# nRF51822.net
KiCad netlist of a schematic drawn in EAGLE
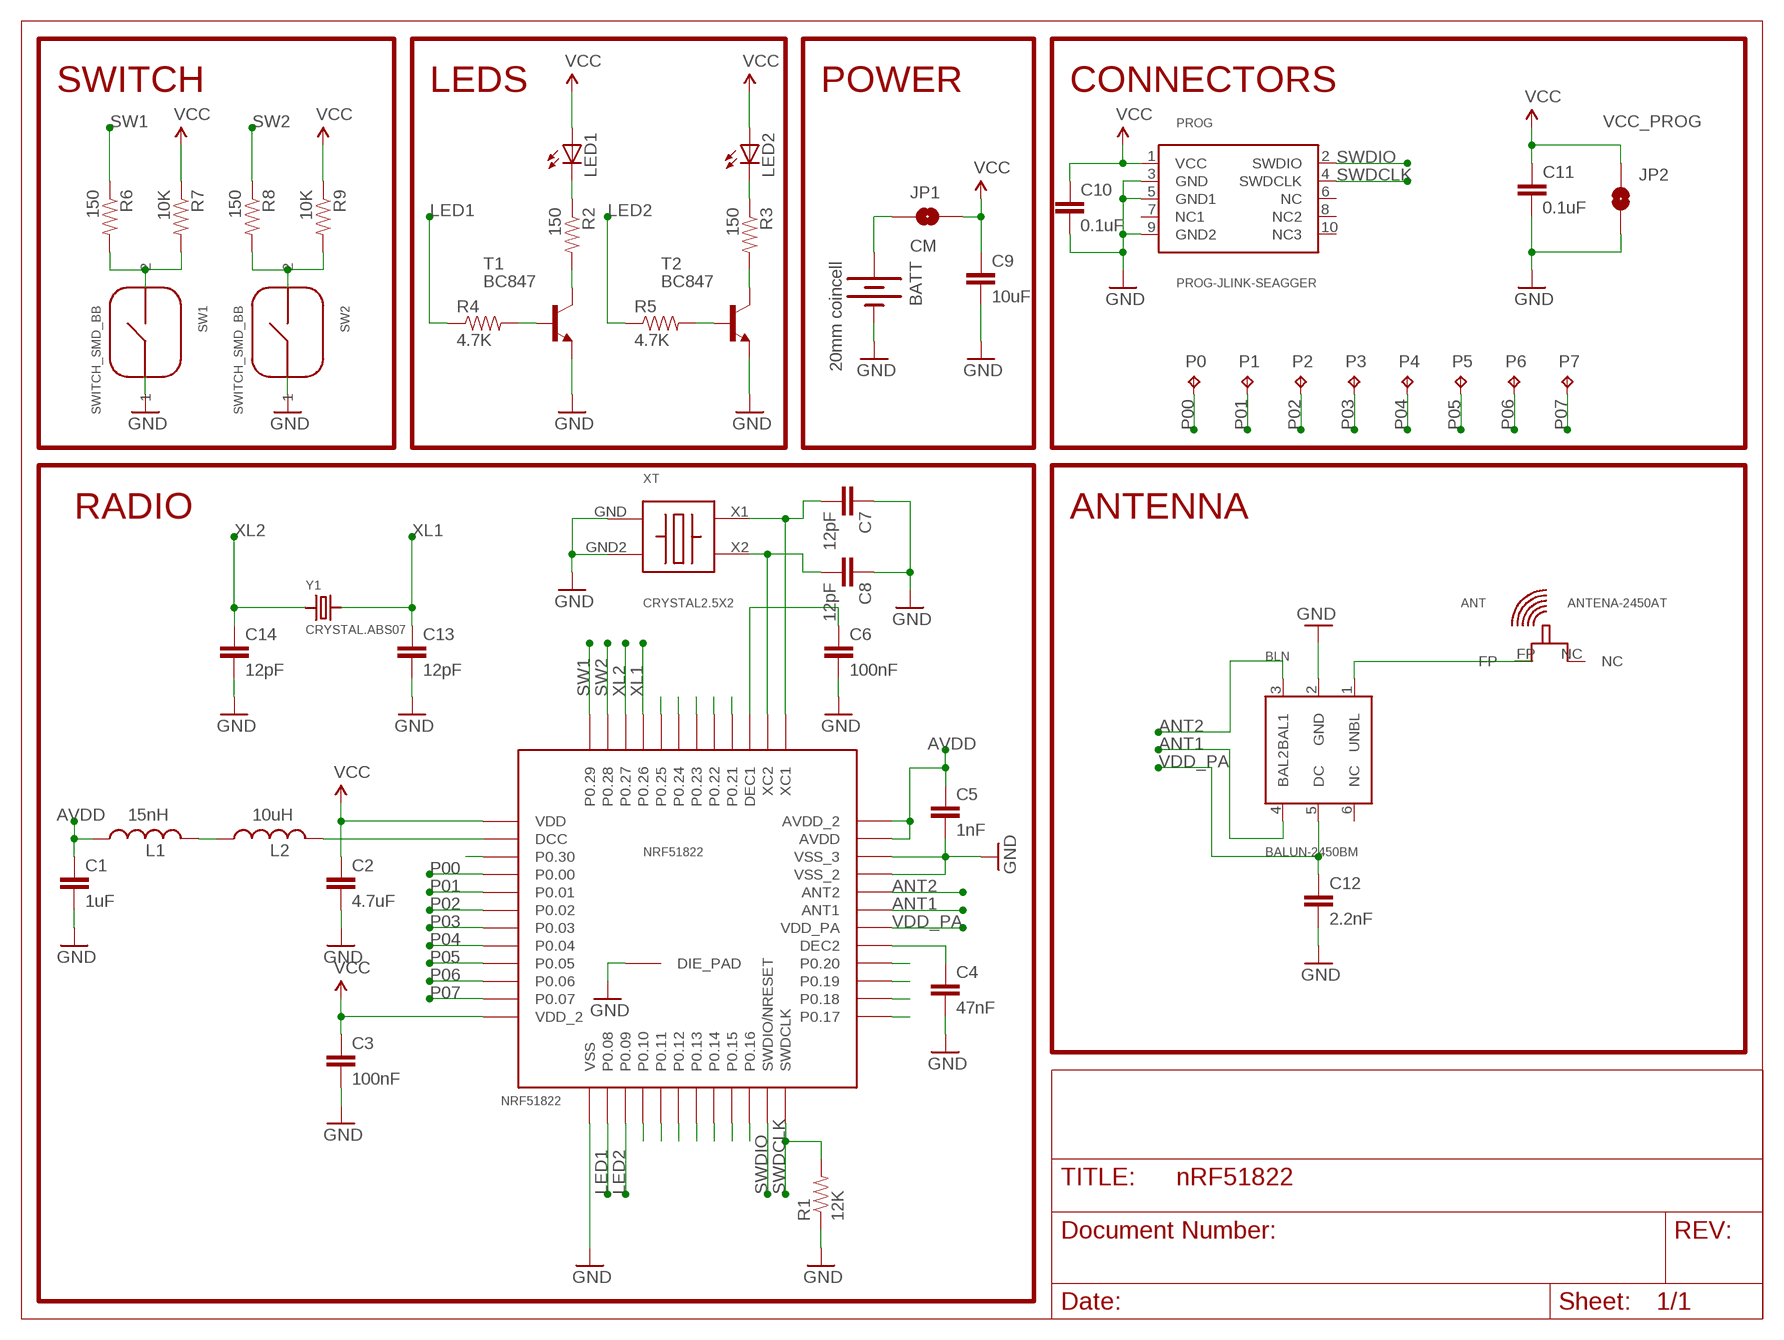
[diagram p0: schematic, sheet 1]

(export (version "E")
  (design (tool "Eeschema 10.0.6"))
  (components
    (comp (ref "ANT")
      (value "ANTENA-2450AT")
      (footprint "eagle-import:2450AT18B100")
      (libsource (lib "eagle-import") (part "ANTENA-2450AT"))
    )
    (comp (ref "BATT")
      (value "20mm coincell")
      (footprint "eagle-import:BATTCON_20MM_4LEGS_OVERPASTE")
      (libsource (lib "eagle-import") (part "BATTERY20MM_4LEGS_OVERPASTE"))
    )
    (comp (ref "BLN")
      (value "BALUN-2450BM")
      (footprint "eagle-import:2450BM14A0002")
      (libsource (lib "eagle-import") (part "BALUN-2450BM"))
    )
    (comp (ref "C1")
      (value "1uF")
      (footprint "eagle-import:0603-CAP")
      (libsource (lib "eagle-import") (part "CAP0603-CAP"))
    )
    (comp (ref "C2")
      (value "4.7uF")
      (footprint "eagle-import:0603-CAP")
      (libsource (lib "eagle-import") (part "CAP0603-CAP"))
    )
    (comp (ref "C3")
      (value "100nF")
      (footprint "eagle-import:0603-CAP")
      (libsource (lib "eagle-import") (part "CAP0603-CAP"))
    )
    (comp (ref "C4")
      (value "47nF")
      (footprint "eagle-import:0603-CAP")
      (libsource (lib "eagle-import") (part "CAP0603-CAP"))
    )
    (comp (ref "C5")
      (value "1nF")
      (footprint "eagle-import:0603-CAP")
      (libsource (lib "eagle-import") (part "CAP0603-CAP"))
    )
    (comp (ref "C6")
      (value "100nF")
      (footprint "eagle-import:0603-CAP")
      (libsource (lib "eagle-import") (part "CAP0603-CAP"))
    )
    (comp (ref "C7")
      (value "12pF")
      (footprint "eagle-import:0603-CAP")
      (libsource (lib "eagle-import") (part "CAP0603-CAP"))
    )
    (comp (ref "C8")
      (value "12pF")
      (footprint "eagle-import:0603-CAP")
      (libsource (lib "eagle-import") (part "CAP0603-CAP"))
    )
    (comp (ref "C9")
      (value "10uF")
      (footprint "eagle-import:0603-CAP")
      (libsource (lib "eagle-import") (part "CAP0603-CAP"))
    )
    (comp (ref "C10")
      (value "0.1uF")
      (footprint "eagle-import:0603-CAP")
      (libsource (lib "eagle-import") (part "CAP0603-CAP"))
    )
    (comp (ref "C11")
      (value "0.1uF")
      (footprint "eagle-import:0603-CAP")
      (libsource (lib "eagle-import") (part "CAP0603-CAP"))
    )
    (comp (ref "C12")
      (value "2.2nF")
      (footprint "eagle-import:0603-CAP")
      (libsource (lib "eagle-import") (part "CAP0603-CAP"))
    )
    (comp (ref "C13")
      (value "12pF")
      (footprint "eagle-import:0603-CAP")
      (libsource (lib "eagle-import") (part "CAP0603-CAP"))
    )
    (comp (ref "C14")
      (value "12pF")
      (footprint "eagle-import:0603-CAP")
      (libsource (lib "eagle-import") (part "CAP0603-CAP"))
    )
    (comp (ref "JP1")
      (value "CM")
      (footprint "eagle-import:JUMP-0.05-SMD")
      (libsource (lib "eagle-import") (part "JUMP_SMDPITCH_0.05"))
    )
    (comp (ref "JP2")
      (value "VCC_PROG")
      (footprint "eagle-import:JUMP-0.05-SMD")
      (libsource (lib "eagle-import") (part "JUMP_SMDPITCH_0.05"))
    )
    (comp (ref "L1")
      (value "15nH")
      (footprint "eagle-import:0603")
      (libsource (lib "eagle-import") (part "INDUCTOR0603"))
    )
    (comp (ref "L2")
      (value "10uH")
      (footprint "eagle-import:0603")
      (libsource (lib "eagle-import") (part "INDUCTOR0603"))
    )
    (comp (ref "LED1")
      (value "LED0603")
      (footprint "eagle-import:LED-0603")
      (libsource (lib "eagle-import") (part "LED0603"))
    )
    (comp (ref "LED2")
      (value "LED0603")
      (footprint "eagle-import:LED-0603")
      (libsource (lib "eagle-import") (part "LED0603"))
    )
    (comp (ref "NRF51822")
      (value "NRF51822")
      (footprint "eagle-import:QFN48")
      (libsource (lib "eagle-import") (part "NRF51822"))
    )
    (comp (ref "P0")
      (value "TPB1,27")
      (footprint "eagle-import:B1,27")
      (libsource (lib "eagle-import") (part "TPB1,27"))
    )
    (comp (ref "P1")
      (value "TPB1,27")
      (footprint "eagle-import:B1,27")
      (libsource (lib "eagle-import") (part "TPB1,27"))
    )
    (comp (ref "P2")
      (value "TPB1,27")
      (footprint "eagle-import:B1,27")
      (libsource (lib "eagle-import") (part "TPB1,27"))
    )
    (comp (ref "P3")
      (value "TPB1,27")
      (footprint "eagle-import:B1,27")
      (libsource (lib "eagle-import") (part "TPB1,27"))
    )
    (comp (ref "P4")
      (value "TPB1,27")
      (footprint "eagle-import:B1,27")
      (libsource (lib "eagle-import") (part "TPB1,27"))
    )
    (comp (ref "P5")
      (value "TPB1,27")
      (footprint "eagle-import:B1,27")
      (libsource (lib "eagle-import") (part "TPB1,27"))
    )
    (comp (ref "P6")
      (value "TPB1,27")
      (footprint "eagle-import:B1,27")
      (libsource (lib "eagle-import") (part "TPB1,27"))
    )
    (comp (ref "P7")
      (value "TPB1,27")
      (footprint "eagle-import:B1,27")
      (libsource (lib "eagle-import") (part "TPB1,27"))
    )
    (comp (ref "PROG")
      (value "PROG-JLINK-SEAGGER")
      (footprint "eagle-import:M50-3600742")
      (libsource (lib "eagle-import") (part "PROG-JLINK-SEAGGER"))
    )
    (comp (ref "R1")
      (value "12K")
      (footprint "eagle-import:0603-RES")
      (libsource (lib "eagle-import") (part "RESISTOR0603-RES"))
    )
    (comp (ref "R2")
      (value "150")
      (footprint "eagle-import:0603-RES")
      (libsource (lib "eagle-import") (part "RESISTOR0603-RES"))
    )
    (comp (ref "R3")
      (value "150")
      (footprint "eagle-import:0603-RES")
      (libsource (lib "eagle-import") (part "RESISTOR0603-RES"))
    )
    (comp (ref "R4")
      (value "4.7K")
      (footprint "eagle-import:0603-RES")
      (libsource (lib "eagle-import") (part "RESISTOR0603-RES"))
    )
    (comp (ref "R5")
      (value "4.7K")
      (footprint "eagle-import:0603-RES")
      (libsource (lib "eagle-import") (part "RESISTOR0603-RES"))
    )
    (comp (ref "R6")
      (value "150")
      (footprint "eagle-import:0603-RES")
      (libsource (lib "eagle-import") (part "RESISTOR0603-RES"))
    )
    (comp (ref "R7")
      (value "10K")
      (footprint "eagle-import:0603-RES")
      (libsource (lib "eagle-import") (part "RESISTOR0603-RES"))
    )
    (comp (ref "R8")
      (value "150")
      (footprint "eagle-import:0603-RES")
      (libsource (lib "eagle-import") (part "RESISTOR0603-RES"))
    )
    (comp (ref "R9")
      (value "10K")
      (footprint "eagle-import:0603-RES")
      (libsource (lib "eagle-import") (part "RESISTOR0603-RES"))
    )
    (comp (ref "SW1")
      (value "SWITCH_SMD_BB")
      (footprint "eagle-import:SWITCH3X2.5")
      (libsource (lib "eagle-import") (part "SWITCH_SMD_BB"))
    )
    (comp (ref "SW2")
      (value "SWITCH_SMD_BB")
      (footprint "eagle-import:SWITCH3X2.5")
      (libsource (lib "eagle-import") (part "SWITCH_SMD_BB"))
    )
    (comp (ref "T1")
      (value "BC847")
      (footprint "eagle-import:SOT23")
      (libsource (lib "eagle-import") (part "BC847"))
    )
    (comp (ref "T2")
      (value "BC847")
      (footprint "eagle-import:SOT23")
      (libsource (lib "eagle-import") (part "BC847"))
    )
    (comp (ref "XT")
      (value "CRYSTAL2.5X2")
      (footprint "eagle-import:2.5X2MM")
      (libsource (lib "eagle-import") (part "CRYSTAL2.5X2"))
    )
    (comp (ref "Y1")
      (value "CRYSTAL.ABS07")
      (footprint "eagle-import:ABS07")
      (libsource (lib "eagle-import") (part "CRYSTAL.ABS07"))
    )
  )
  (nets
    (net (code "1") (name "/ANT1") (class "Default")
      (node (ref "BLN") (pin "4") (pinfunction "BAL2_4") (pintype "bidirectional"))
      (node (ref "NRF51822") (pin "31") (pinfunction "ANT1_31") (pintype "bidirectional"))
    )
    (net (code "2") (name "/ANT2") (class "Default")
      (node (ref "BLN") (pin "3") (pinfunction "BAL1_3") (pintype "bidirectional"))
      (node (ref "NRF51822") (pin "32") (pinfunction "ANT2_32") (pintype "bidirectional"))
    )
    (net (code "3") (name "/AVDD") (class "Default")
      (node (ref "C1") (pin "1") (pinfunction "1_1") (pintype "passive"))
      (node (ref "C5") (pin "1") (pinfunction "1_1") (pintype "passive"))
      (node (ref "L1") (pin "1") (pinfunction "1_1") (pintype "passive"))
      (node (ref "NRF51822") (pin "35") (pinfunction "AVDD_35") (pintype "bidirectional"))
      (node (ref "NRF51822") (pin "36") (pinfunction "AVDD_2_36") (pintype "bidirectional"))
    )
    (net (code "4") (name "/LED1") (class "Default")
      (node (ref "NRF51822") (pin "14") (pinfunction "P0.08_14") (pintype "bidirectional"))
      (node (ref "R4") (pin "1") (pinfunction "1_1") (pintype "passive"))
    )
    (net (code "5") (name "/LED2") (class "Default")
      (node (ref "NRF51822") (pin "15") (pinfunction "P0.09_15") (pintype "bidirectional"))
      (node (ref "R5") (pin "1") (pinfunction "1_1") (pintype "passive"))
    )
    (net (code "6") (name "/P00") (class "Default")
      (node (ref "NRF51822") (pin "4") (pinfunction "P0.00_4") (pintype "bidirectional"))
      (node (ref "P0") (pin "TP") (pinfunction "TP_TP") (pintype "input"))
    )
    (net (code "7") (name "/P01") (class "Default")
      (node (ref "NRF51822") (pin "5") (pinfunction "P0.01_5") (pintype "bidirectional"))
      (node (ref "P1") (pin "TP") (pinfunction "TP_TP") (pintype "input"))
    )
    (net (code "8") (name "/P02") (class "Default")
      (node (ref "NRF51822") (pin "6") (pinfunction "P0.02_6") (pintype "bidirectional"))
      (node (ref "P2") (pin "TP") (pinfunction "TP_TP") (pintype "input"))
    )
    (net (code "9") (name "/P03") (class "Default")
      (node (ref "NRF51822") (pin "7") (pinfunction "P0.03_7") (pintype "bidirectional"))
      (node (ref "P3") (pin "TP") (pinfunction "TP_TP") (pintype "input"))
    )
    (net (code "10") (name "/P04") (class "Default")
      (node (ref "NRF51822") (pin "8") (pinfunction "P0.04_8") (pintype "bidirectional"))
      (node (ref "P4") (pin "TP") (pinfunction "TP_TP") (pintype "input"))
    )
    (net (code "11") (name "/P05") (class "Default")
      (node (ref "NRF51822") (pin "9") (pinfunction "P0.05_9") (pintype "bidirectional"))
      (node (ref "P5") (pin "TP") (pinfunction "TP_TP") (pintype "input"))
    )
    (net (code "12") (name "/P06") (class "Default")
      (node (ref "NRF51822") (pin "10") (pinfunction "P0.06_10") (pintype "bidirectional"))
      (node (ref "P6") (pin "TP") (pinfunction "TP_TP") (pintype "input"))
    )
    (net (code "13") (name "/P07") (class "Default")
      (node (ref "NRF51822") (pin "11") (pinfunction "P0.07_11") (pintype "bidirectional"))
      (node (ref "P7") (pin "TP") (pinfunction "TP_TP") (pintype "input"))
    )
    (net (code "14") (name "/SW1") (class "Default")
      (node (ref "NRF51822") (pin "48") (pinfunction "P0.29_48") (pintype "bidirectional"))
      (node (ref "R6") (pin "1") (pinfunction "1_1") (pintype "passive"))
    )
    (net (code "15") (name "/SW2") (class "Default")
      (node (ref "NRF51822") (pin "47") (pinfunction "P0.28_47") (pintype "bidirectional"))
      (node (ref "R8") (pin "1") (pinfunction "1_1") (pintype "passive"))
    )
    (net (code "16") (name "/SWDCLK") (class "Default")
      (node (ref "NRF51822") (pin "24") (pinfunction "SWDCLK_24") (pintype "bidirectional"))
      (node (ref "PROG") (pin "4") (pinfunction "SWDCLK_4") (pintype "bidirectional"))
      (node (ref "R1") (pin "2") (pinfunction "2_2") (pintype "passive"))
    )
    (net (code "17") (name "/SWDIO") (class "Default")
      (node (ref "NRF51822") (pin "23") (pinfunction "SWDIO/NRESET_23") (pintype "bidirectional"))
      (node (ref "PROG") (pin "2") (pinfunction "SWDIO_2") (pintype "bidirectional"))
    )
    (net (code "18") (name "/VDD_PA") (class "Default")
      (node (ref "BLN") (pin "5") (pinfunction "DC_5") (pintype "bidirectional"))
      (node (ref "C12") (pin "1") (pinfunction "1_1") (pintype "passive"))
      (node (ref "NRF51822") (pin "30") (pinfunction "VDD_PA_30") (pintype "bidirectional"))
    )
    (net (code "19") (name "/XL1") (class "Default")
      (node (ref "C13") (pin "1") (pinfunction "1_1") (pintype "passive"))
      (node (ref "NRF51822") (pin "45") (pinfunction "P0.26_45") (pintype "bidirectional"))
      (node (ref "Y1") (pin "2") (pinfunction "2_2") (pintype "passive"))
    )
    (net (code "20") (name "/XL2") (class "Default")
      (node (ref "C14") (pin "1") (pinfunction "1_1") (pintype "passive"))
      (node (ref "NRF51822") (pin "46") (pinfunction "P0.27_46") (pintype "bidirectional"))
      (node (ref "Y1") (pin "1") (pinfunction "1_1") (pintype "passive"))
    )
    (net (code "21") (name "GND") (class "Default")
      (node (ref "BATT") (pin "2") (pinfunction "-_2") (pintype "power_in"))
      (node (ref "BLN") (pin "2") (pinfunction "GND_2") (pintype "bidirectional"))
      (node (ref "C1") (pin "2") (pinfunction "2_2") (pintype "passive"))
      (node (ref "C10") (pin "2") (pinfunction "2_2") (pintype "passive"))
      (node (ref "C11") (pin "2") (pinfunction "2_2") (pintype "passive"))
      (node (ref "C12") (pin "2") (pinfunction "2_2") (pintype "passive"))
      (node (ref "C13") (pin "2") (pinfunction "2_2") (pintype "passive"))
      (node (ref "C14") (pin "2") (pinfunction "2_2") (pintype "passive"))
      (node (ref "C2") (pin "2") (pinfunction "2_2") (pintype "passive"))
      (node (ref "C3") (pin "2") (pinfunction "2_2") (pintype "passive"))
      (node (ref "C4") (pin "2") (pinfunction "2_2") (pintype "passive"))
      (node (ref "C5") (pin "2") (pinfunction "2_2") (pintype "passive"))
      (node (ref "C6") (pin "2") (pinfunction "2_2") (pintype "passive"))
      (node (ref "C7") (pin "1") (pinfunction "1_1") (pintype "passive"))
      (node (ref "C8") (pin "1") (pinfunction "1_1") (pintype "passive"))
      (node (ref "C9") (pin "2") (pinfunction "2_2") (pintype "passive"))
      (node (ref "JP2") (pin "P$2") (pinfunction "2_P$2") (pintype "passive"))
      (node (ref "NRF51822") (pin "13") (pinfunction "VSS_13") (pintype "bidirectional"))
      (node (ref "NRF51822") (pin "33") (pinfunction "VSS_2_33") (pintype "bidirectional"))
      (node (ref "NRF51822") (pin "34") (pinfunction "VSS_3_34") (pintype "bidirectional"))
      (node (ref "NRF51822") (pin "GND") (pinfunction "DIE_PAD_GND") (pintype "bidirectional"))
      (node (ref "PROG") (pin "3") (pinfunction "GND_3") (pintype "bidirectional"))
      (node (ref "PROG") (pin "5") (pinfunction "GND1_5") (pintype "bidirectional"))
      (node (ref "PROG") (pin "9") (pinfunction "GND2_9") (pintype "bidirectional"))
      (node (ref "R1") (pin "1") (pinfunction "1_1") (pintype "passive"))
      (node (ref "SW1") (pin "1") (pinfunction "1_1") (pintype "bidirectional"))
      (node (ref "SW2") (pin "1") (pinfunction "1_1") (pintype "bidirectional"))
      (node (ref "T1") (pin "2") (pinfunction "E_2") (pintype "passive"))
      (node (ref "T2") (pin "2") (pinfunction "E_2") (pintype "passive"))
      (node (ref "XT") (pin "GND") (pinfunction "GND_GND") (pintype "bidirectional"))
      (node (ref "XT") (pin "GND2") (pinfunction "GND2_GND2") (pintype "bidirectional"))
    )
    (net (code "22") (name "Net-(BATT-+)") (class "Default")
      (node (ref "BATT") (pin "1") (pinfunction "+_1") (pintype "power_in"))
      (node (ref "JP1") (pin "P$1") (pinfunction "1_P$1") (pintype "passive"))
    )
    (net (code "23") (name "Net-(BLN-UNBL)") (class "Default")
      (node (ref "ANT") (pin "FP") (pinfunction "FP_FP") (pintype "bidirectional"))
      (node (ref "BLN") (pin "1") (pinfunction "UNBL_1") (pintype "bidirectional"))
    )
    (net (code "24") (name "Net-(L1-Pad2)") (class "Default")
      (node (ref "L1") (pin "2") (pinfunction "2_2") (pintype "passive"))
      (node (ref "L2") (pin "1") (pinfunction "1_1") (pintype "passive"))
    )
    (net (code "25") (name "Net-(LED1-PadC)") (class "Default")
      (node (ref "LED1") (pin "C") (pinfunction "C_C") (pintype "passive"))
      (node (ref "R2") (pin "1") (pinfunction "1_1") (pintype "passive"))
    )
    (net (code "26") (name "Net-(LED2-PadC)") (class "Default")
      (node (ref "LED2") (pin "C") (pinfunction "C_C") (pintype "passive"))
      (node (ref "R3") (pin "1") (pinfunction "1_1") (pintype "passive"))
    )
    (net (code "27") (name "Net-(NRF51822-DCC)") (class "Default")
      (node (ref "L2") (pin "2") (pinfunction "2_2") (pintype "passive"))
      (node (ref "NRF51822") (pin "2") (pinfunction "DCC_2") (pintype "bidirectional"))
    )
    (net (code "28") (name "Net-(NRF51822-DEC1)") (class "Default")
      (node (ref "C6") (pin "1") (pinfunction "1_1") (pintype "passive"))
      (node (ref "NRF51822") (pin "39") (pinfunction "DEC1_39") (pintype "bidirectional"))
    )
    (net (code "29") (name "Net-(NRF51822-DEC2)") (class "Default")
      (node (ref "C4") (pin "1") (pinfunction "1_1") (pintype "passive"))
      (node (ref "NRF51822") (pin "29") (pinfunction "DEC2_29") (pintype "bidirectional"))
    )
    (net (code "30") (name "Net-(NRF51822-XC1)") (class "Default")
      (node (ref "C7") (pin "2") (pinfunction "2_2") (pintype "passive"))
      (node (ref "NRF51822") (pin "37") (pinfunction "XC1_37") (pintype "bidirectional"))
      (node (ref "XT") (pin "X1") (pinfunction "X1_X1") (pintype "bidirectional"))
    )
    (net (code "31") (name "Net-(NRF51822-XC2)") (class "Default")
      (node (ref "C8") (pin "2") (pinfunction "2_2") (pintype "passive"))
      (node (ref "NRF51822") (pin "38") (pinfunction "XC2_38") (pintype "bidirectional"))
      (node (ref "XT") (pin "X2") (pinfunction "X2_X2") (pintype "bidirectional"))
    )
    (net (code "32") (name "Net-(R6-Pad2)") (class "Default")
      (node (ref "R6") (pin "2") (pinfunction "2_2") (pintype "passive"))
      (node (ref "R7") (pin "2") (pinfunction "2_2") (pintype "passive"))
      (node (ref "SW1") (pin "2") (pinfunction "2_2") (pintype "bidirectional"))
    )
    (net (code "33") (name "Net-(R8-Pad2)") (class "Default")
      (node (ref "R8") (pin "2") (pinfunction "2_2") (pintype "passive"))
      (node (ref "R9") (pin "2") (pinfunction "2_2") (pintype "passive"))
      (node (ref "SW2") (pin "2") (pinfunction "2_2") (pintype "bidirectional"))
    )
    (net (code "34") (name "Net-(T1-B)") (class "Default")
      (node (ref "R4") (pin "2") (pinfunction "2_2") (pintype "passive"))
      (node (ref "T1") (pin "1") (pinfunction "B_1") (pintype "passive"))
    )
    (net (code "35") (name "Net-(T1-C)") (class "Default")
      (node (ref "R2") (pin "2") (pinfunction "2_2") (pintype "passive"))
      (node (ref "T1") (pin "3") (pinfunction "C_3") (pintype "passive"))
    )
    (net (code "36") (name "Net-(T2-B)") (class "Default")
      (node (ref "R5") (pin "2") (pinfunction "2_2") (pintype "passive"))
      (node (ref "T2") (pin "1") (pinfunction "B_1") (pintype "passive"))
    )
    (net (code "37") (name "Net-(T2-C)") (class "Default")
      (node (ref "R3") (pin "2") (pinfunction "2_2") (pintype "passive"))
      (node (ref "T2") (pin "3") (pinfunction "C_3") (pintype "passive"))
    )
    (net (code "38") (name "VCC") (class "Default")
      (node (ref "C10") (pin "1") (pinfunction "1_1") (pintype "passive"))
      (node (ref "C11") (pin "1") (pinfunction "1_1") (pintype "passive"))
      (node (ref "C2") (pin "1") (pinfunction "1_1") (pintype "passive"))
      (node (ref "C3") (pin "1") (pinfunction "1_1") (pintype "passive"))
      (node (ref "C9") (pin "1") (pinfunction "1_1") (pintype "passive"))
      (node (ref "JP1") (pin "P$2") (pinfunction "2_P$2") (pintype "passive"))
      (node (ref "JP2") (pin "P$1") (pinfunction "1_P$1") (pintype "passive"))
      (node (ref "LED1") (pin "A") (pinfunction "A_A") (pintype "passive"))
      (node (ref "LED2") (pin "A") (pinfunction "A_A") (pintype "passive"))
      (node (ref "NRF51822") (pin "1") (pinfunction "VDD_1") (pintype "bidirectional"))
      (node (ref "NRF51822") (pin "12") (pinfunction "VDD_2_12") (pintype "bidirectional"))
      (node (ref "PROG") (pin "1") (pinfunction "VCC_1") (pintype "bidirectional"))
      (node (ref "R7") (pin "1") (pinfunction "1_1") (pintype "passive"))
      (node (ref "R9") (pin "1") (pinfunction "1_1") (pintype "passive"))
    )
    (net (code "39") (name "unconnected-(ANT-PadNC)") (class "Default")
      (node (ref "ANT") (pin "NC") (pinfunction "NC_NC") (pintype "bidirectional"))
    )
    (net (code "40") (name "unconnected-(BLN-NC-Pad6)") (class "Default")
      (node (ref "BLN") (pin "6") (pinfunction "NC_6") (pintype "bidirectional"))
    )
    (net (code "41") (name "unconnected-(NRF51822-P0.10-Pad16)") (class "Default")
      (node (ref "NRF51822") (pin "16") (pinfunction "P0.10_16") (pintype "bidirectional"))
    )
    (net (code "42") (name "unconnected-(NRF51822-P0.11-Pad17)") (class "Default")
      (node (ref "NRF51822") (pin "17") (pinfunction "P0.11_17") (pintype "bidirectional"))
    )
    (net (code "43") (name "unconnected-(NRF51822-P0.12-Pad18)") (class "Default")
      (node (ref "NRF51822") (pin "18") (pinfunction "P0.12_18") (pintype "bidirectional"))
    )
    (net (code "44") (name "unconnected-(NRF51822-P0.13-Pad19)") (class "Default")
      (node (ref "NRF51822") (pin "19") (pinfunction "P0.13_19") (pintype "bidirectional"))
    )
    (net (code "45") (name "unconnected-(NRF51822-P0.14-Pad20)") (class "Default")
      (node (ref "NRF51822") (pin "20") (pinfunction "P0.14_20") (pintype "bidirectional"))
    )
    (net (code "46") (name "unconnected-(NRF51822-P0.15-Pad21)") (class "Default")
      (node (ref "NRF51822") (pin "21") (pinfunction "P0.15_21") (pintype "bidirectional"))
    )
    (net (code "47") (name "unconnected-(NRF51822-P0.16-Pad22)") (class "Default")
      (node (ref "NRF51822") (pin "22") (pinfunction "P0.16_22") (pintype "bidirectional"))
    )
    (net (code "48") (name "unconnected-(NRF51822-P0.17-Pad25)") (class "Default")
      (node (ref "NRF51822") (pin "25") (pinfunction "P0.17_25") (pintype "bidirectional"))
    )
    (net (code "49") (name "unconnected-(NRF51822-P0.18-Pad26)") (class "Default")
      (node (ref "NRF51822") (pin "26") (pinfunction "P0.18_26") (pintype "bidirectional"))
    )
    (net (code "50") (name "unconnected-(NRF51822-P0.19-Pad27)") (class "Default")
      (node (ref "NRF51822") (pin "27") (pinfunction "P0.19_27") (pintype "bidirectional"))
    )
    (net (code "51") (name "unconnected-(NRF51822-P0.20-Pad28)") (class "Default")
      (node (ref "NRF51822") (pin "28") (pinfunction "P0.20_28") (pintype "bidirectional"))
    )
    (net (code "52") (name "unconnected-(NRF51822-P0.21-Pad40)") (class "Default")
      (node (ref "NRF51822") (pin "40") (pinfunction "P0.21_40") (pintype "bidirectional"))
    )
    (net (code "53") (name "unconnected-(NRF51822-P0.22-Pad41)") (class "Default")
      (node (ref "NRF51822") (pin "41") (pinfunction "P0.22_41") (pintype "bidirectional"))
    )
    (net (code "54") (name "unconnected-(NRF51822-P0.23-Pad42)") (class "Default")
      (node (ref "NRF51822") (pin "42") (pinfunction "P0.23_42") (pintype "bidirectional"))
    )
    (net (code "55") (name "unconnected-(NRF51822-P0.24-Pad43)") (class "Default")
      (node (ref "NRF51822") (pin "43") (pinfunction "P0.24_43") (pintype "bidirectional"))
    )
    (net (code "56") (name "unconnected-(NRF51822-P0.25-Pad44)") (class "Default")
      (node (ref "NRF51822") (pin "44") (pinfunction "P0.25_44") (pintype "bidirectional"))
    )
    (net (code "57") (name "unconnected-(NRF51822-P0.30-Pad3)") (class "Default")
      (node (ref "NRF51822") (pin "3") (pinfunction "P0.30_3") (pintype "bidirectional"))
    )
    (net (code "58") (name "unconnected-(PROG-NC-Pad6)") (class "Default")
      (node (ref "PROG") (pin "6") (pinfunction "NC_6") (pintype "bidirectional"))
    )
    (net (code "59") (name "unconnected-(PROG-NC1-Pad7)") (class "Default")
      (node (ref "PROG") (pin "7") (pinfunction "NC1_7") (pintype "bidirectional"))
    )
    (net (code "60") (name "unconnected-(PROG-NC2-Pad8)") (class "Default")
      (node (ref "PROG") (pin "8") (pinfunction "NC2_8") (pintype "bidirectional"))
    )
    (net (code "61") (name "unconnected-(PROG-NC3-Pad10)") (class "Default")
      (node (ref "PROG") (pin "10") (pinfunction "NC3_10") (pintype "bidirectional"))
    )
  )
)
